# droneMaster.net
KiCad netlist of a schematic drawn in EAGLE
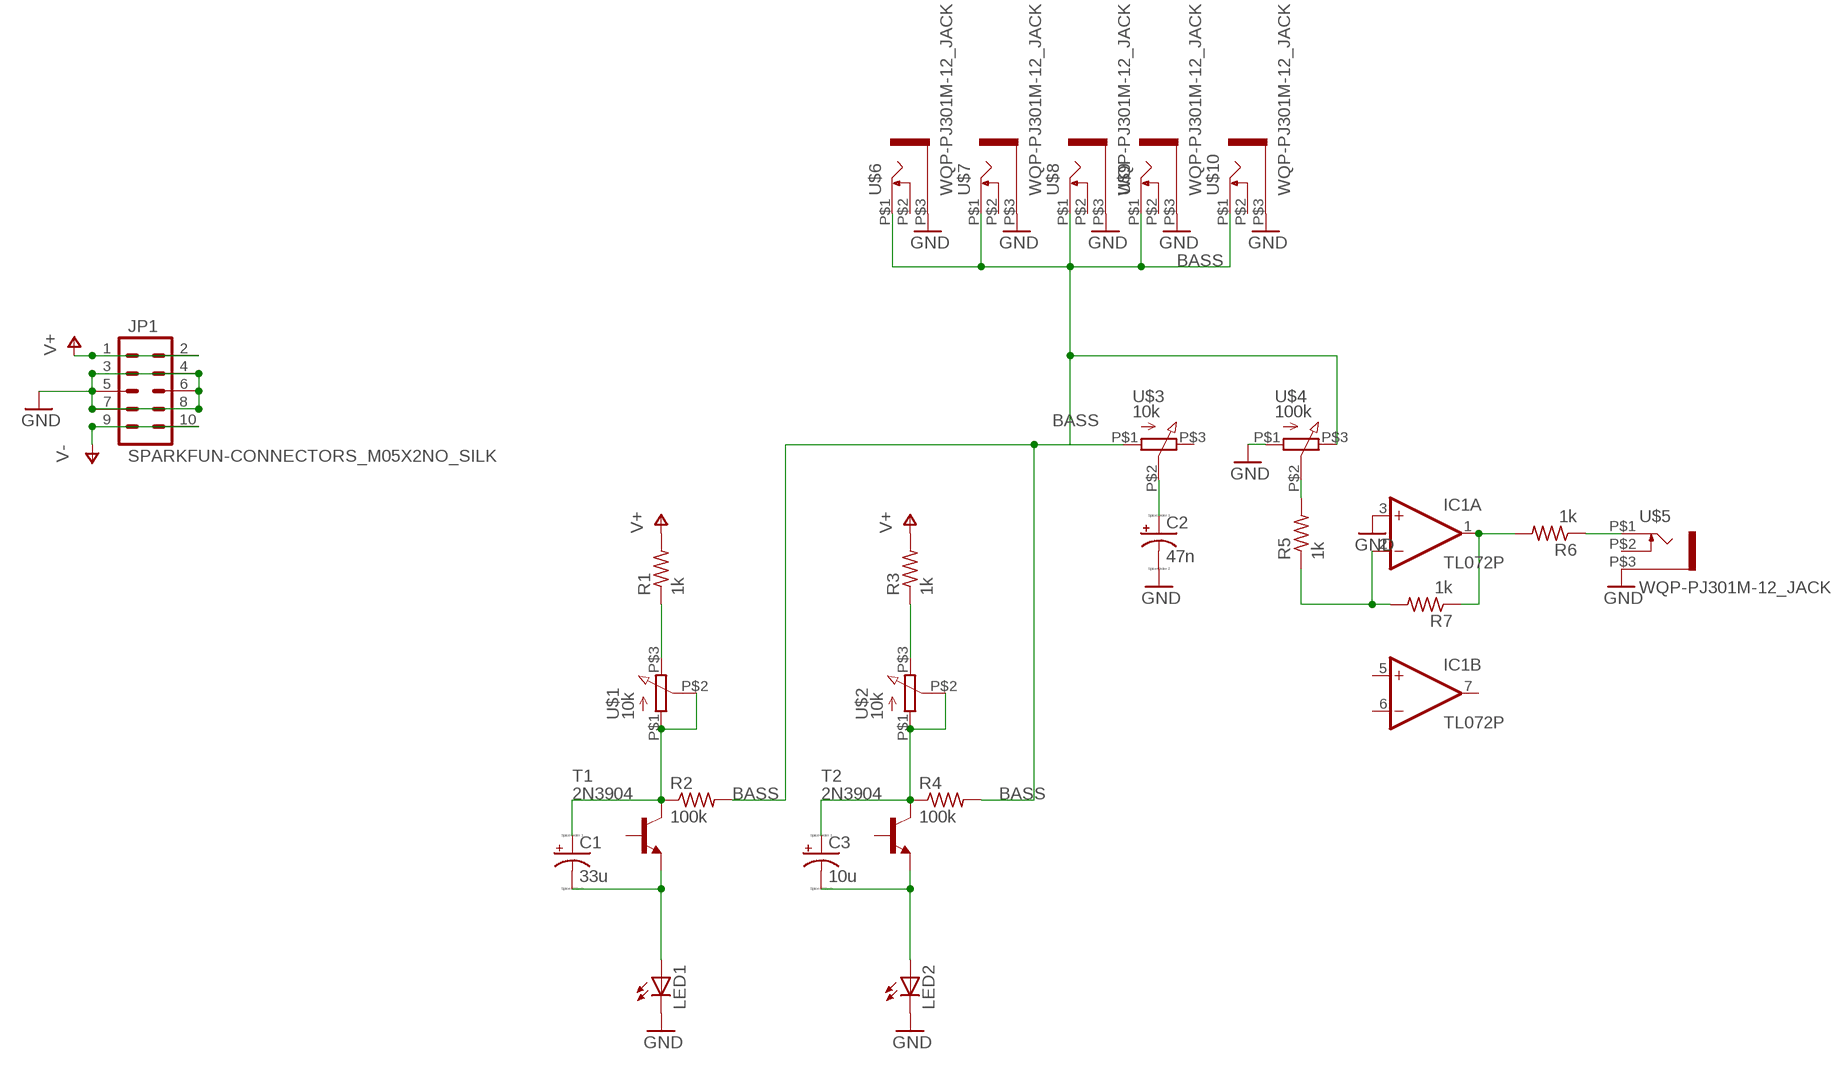
[diagram p0: schematic, sheet 1]

(export (version "E")
  (design (tool "Eeschema 10.0.6"))
  (components
    (comp (ref "C1")
      (value "33u")
      (footprint "eagle-import:E2,5-7")
      (libsource (lib "eagle-import") (part "CPOL-USE2.5-7"))
    )
    (comp (ref "C2")
      (value "47n")
      (footprint "eagle-import:E2,5-7")
      (libsource (lib "eagle-import") (part "CPOL-USE2.5-7"))
    )
    (comp (ref "C3")
      (value "10u")
      (footprint "eagle-import:E2,5-7")
      (libsource (lib "eagle-import") (part "CPOL-USE2.5-7"))
    )
    (comp (ref "IC1")
      (value "TL072P")
      (footprint "eagle-import:DIL08")
      (libsource (lib "eagle-import") (part "TL072P"))
    )
    (comp (ref "JP1")
      (value "SPARKFUN-CONNECTORS_M05X2NO_SILK")
      (footprint "eagle-import:SPARKFUN-CONNECTORS_2X5_NOSILK")
      (libsource (lib "eagle-import") (part "SPARKFUN-CONNECTORS_M05X2NO_SILK"))
    )
    (comp (ref "LED1")
      (value "LED5MM")
      (footprint "eagle-import:LED5MM")
      (libsource (lib "eagle-import") (part "LED5MM"))
    )
    (comp (ref "LED2")
      (value "LED5MM")
      (footprint "eagle-import:LED5MM")
      (libsource (lib "eagle-import") (part "LED5MM"))
    )
    (comp (ref "R1")
      (value "1k")
      (footprint "eagle-import:0204_7")
      (libsource (lib "eagle-import") (part "R-US_0204/7"))
    )
    (comp (ref "R2")
      (value "100k")
      (footprint "eagle-import:0204_7")
      (libsource (lib "eagle-import") (part "R-US_0204/7"))
    )
    (comp (ref "R3")
      (value "1k")
      (footprint "eagle-import:0204_7")
      (libsource (lib "eagle-import") (part "R-US_0204/7"))
    )
    (comp (ref "R4")
      (value "100k")
      (footprint "eagle-import:0204_7")
      (libsource (lib "eagle-import") (part "R-US_0204/7"))
    )
    (comp (ref "R5")
      (value "1k")
      (footprint "eagle-import:0204_7")
      (libsource (lib "eagle-import") (part "R-US_0204/7"))
    )
    (comp (ref "R6")
      (value "1k")
      (footprint "eagle-import:0204_7")
      (libsource (lib "eagle-import") (part "R-US_0204/7"))
    )
    (comp (ref "R7")
      (value "1k")
      (footprint "eagle-import:0204_7")
      (libsource (lib "eagle-import") (part "R-US_0204/7"))
    )
    (comp (ref "T1")
      (value "2N3904")
      (footprint "eagle-import:TO92")
      (libsource (lib "eagle-import") (part "2N3904"))
    )
    (comp (ref "T2")
      (value "2N3904")
      (footprint "eagle-import:TO92")
      (libsource (lib "eagle-import") (part "2N3904"))
    )
    (comp (ref "U$1")
      (value "10k")
      (footprint "eagle-import:INSTRUO_Q-POT")
      (libsource (lib "eagle-import") (part "INSTRUO_Q-POT"))
    )
    (comp (ref "U$2")
      (value "10k")
      (footprint "eagle-import:INSTRUO_Q-POT")
      (libsource (lib "eagle-import") (part "INSTRUO_Q-POT"))
    )
    (comp (ref "U$3")
      (value "10k")
      (footprint "eagle-import:INSTRUO_Q-POT")
      (libsource (lib "eagle-import") (part "INSTRUO_Q-POT"))
    )
    (comp (ref "U$4")
      (value "100k")
      (footprint "eagle-import:INSTRUO_Q-POT")
      (libsource (lib "eagle-import") (part "INSTRUO_Q-POT"))
    )
    (comp (ref "U$5")
      (value "WQP-PJ301M-12_JACK")
      (footprint "eagle-import:WQP-PJ301M-12_JACK")
      (libsource (lib "eagle-import") (part "WQP-PJ301M-12_JACK"))
    )
    (comp (ref "U$6")
      (value "WQP-PJ301M-12_JACK")
      (footprint "eagle-import:WQP-PJ301M-12_JACK")
      (libsource (lib "eagle-import") (part "WQP-PJ301M-12_JACK"))
    )
    (comp (ref "U$7")
      (value "WQP-PJ301M-12_JACK")
      (footprint "eagle-import:WQP-PJ301M-12_JACK")
      (libsource (lib "eagle-import") (part "WQP-PJ301M-12_JACK"))
    )
    (comp (ref "U$8")
      (value "WQP-PJ301M-12_JACK")
      (footprint "eagle-import:WQP-PJ301M-12_JACK")
      (libsource (lib "eagle-import") (part "WQP-PJ301M-12_JACK"))
    )
    (comp (ref "U$9")
      (value "WQP-PJ301M-12_JACK")
      (footprint "eagle-import:WQP-PJ301M-12_JACK")
      (libsource (lib "eagle-import") (part "WQP-PJ301M-12_JACK"))
    )
    (comp (ref "U$10")
      (value "WQP-PJ301M-12_JACK")
      (footprint "eagle-import:WQP-PJ301M-12_JACK")
      (libsource (lib "eagle-import") (part "WQP-PJ301M-12_JACK"))
    )
  )
  (nets
    (net (code "1") (name "/BASS") (class "Default")
      (node (ref "R2") (pin "2") (pinfunction "2_2") (pintype "passive"))
      (node (ref "R4") (pin "2") (pinfunction "2_2") (pintype "passive"))
      (node (ref "U$10") (pin "P$1") (pinfunction "2_P$1") (pintype "passive"))
      (node (ref "U$3") (pin "P$1") (pinfunction "1_P$1") (pintype "passive"))
      (node (ref "U$4") (pin "P$3") (pinfunction "3_P$3") (pintype "passive"))
      (node (ref "U$6") (pin "P$1") (pinfunction "2_P$1") (pintype "passive"))
      (node (ref "U$7") (pin "P$1") (pinfunction "2_P$1") (pintype "passive"))
      (node (ref "U$8") (pin "P$1") (pinfunction "2_P$1") (pintype "passive"))
      (node (ref "U$9") (pin "P$1") (pinfunction "2_P$1") (pintype "passive"))
    )
    (net (code "2") (name "GND") (class "Default")
      (node (ref "C2") (pin "-") (pinfunction "-_-") (pintype "passive"))
      (node (ref "IC1") (pin "3") (pinfunction "+IN_3") (pintype "input"))
      (node (ref "JP1") (pin "3") (pinfunction "3_3") (pintype "passive"))
      (node (ref "JP1") (pin "4") (pinfunction "4_4") (pintype "passive"))
      (node (ref "JP1") (pin "5") (pinfunction "5_5") (pintype "passive"))
      (node (ref "JP1") (pin "6") (pinfunction "6_6") (pintype "passive"))
      (node (ref "JP1") (pin "7") (pinfunction "7_7") (pintype "passive"))
      (node (ref "JP1") (pin "8") (pinfunction "8_8") (pintype "passive"))
      (node (ref "LED1") (pin "K") (pinfunction "C_K") (pintype "passive"))
      (node (ref "LED2") (pin "K") (pinfunction "C_K") (pintype "passive"))
      (node (ref "U$10") (pin "P$3") (pinfunction "1_P$3") (pintype "passive"))
      (node (ref "U$4") (pin "P$1") (pinfunction "1_P$1") (pintype "passive"))
      (node (ref "U$5") (pin "P$3") (pinfunction "1_P$3") (pintype "passive"))
      (node (ref "U$6") (pin "P$3") (pinfunction "1_P$3") (pintype "passive"))
      (node (ref "U$7") (pin "P$3") (pinfunction "1_P$3") (pintype "passive"))
      (node (ref "U$8") (pin "P$3") (pinfunction "1_P$3") (pintype "passive"))
      (node (ref "U$9") (pin "P$3") (pinfunction "1_P$3") (pintype "passive"))
    )
    (net (code "3") (name "Net-(IC1A--IN)") (class "Default")
      (node (ref "IC1") (pin "2") (pinfunction "-IN_2") (pintype "input"))
      (node (ref "R5") (pin "1") (pinfunction "1_1") (pintype "passive"))
      (node (ref "R7") (pin "2") (pinfunction "2_2") (pintype "passive"))
    )
    (net (code "4") (name "Net-(IC1A-OUT)") (class "Default")
      (node (ref "IC1") (pin "1") (pinfunction "OUT_1") (pintype "output"))
      (node (ref "R6") (pin "2") (pinfunction "2_2") (pintype "passive"))
      (node (ref "R7") (pin "1") (pinfunction "1_1") (pintype "passive"))
    )
    (net (code "5") (name "Net-(T1-C)") (class "Default")
      (node (ref "C1") (pin "+") (pinfunction "+_+") (pintype "passive"))
      (node (ref "R2") (pin "1") (pinfunction "1_1") (pintype "passive"))
      (node (ref "T1") (pin "1") (pinfunction "C_1") (pintype "passive"))
      (node (ref "U$1") (pin "P$1") (pinfunction "1_P$1") (pintype "passive"))
      (node (ref "U$1") (pin "P$2") (pinfunction "2_P$2") (pintype "passive"))
    )
    (net (code "6") (name "Net-(T1-E)") (class "Default")
      (node (ref "C1") (pin "-") (pinfunction "-_-") (pintype "passive"))
      (node (ref "LED1") (pin "A") (pinfunction "A_A") (pintype "passive"))
      (node (ref "T1") (pin "3") (pinfunction "E_3") (pintype "passive"))
    )
    (net (code "7") (name "Net-(T2-C)") (class "Default")
      (node (ref "C3") (pin "+") (pinfunction "+_+") (pintype "passive"))
      (node (ref "R4") (pin "1") (pinfunction "1_1") (pintype "passive"))
      (node (ref "T2") (pin "1") (pinfunction "C_1") (pintype "passive"))
      (node (ref "U$2") (pin "P$1") (pinfunction "1_P$1") (pintype "passive"))
      (node (ref "U$2") (pin "P$2") (pinfunction "2_P$2") (pintype "passive"))
    )
    (net (code "8") (name "Net-(T2-E)") (class "Default")
      (node (ref "C3") (pin "-") (pinfunction "-_-") (pintype "passive"))
      (node (ref "LED2") (pin "A") (pinfunction "A_A") (pintype "passive"))
      (node (ref "T2") (pin "3") (pinfunction "E_3") (pintype "passive"))
    )
    (net (code "9") (name "Net-(U$1-3)") (class "Default")
      (node (ref "R1") (pin "1") (pinfunction "1_1") (pintype "passive"))
      (node (ref "U$1") (pin "P$3") (pinfunction "3_P$3") (pintype "passive"))
    )
    (net (code "10") (name "Net-(U$2-3)") (class "Default")
      (node (ref "R3") (pin "1") (pinfunction "1_1") (pintype "passive"))
      (node (ref "U$2") (pin "P$3") (pinfunction "3_P$3") (pintype "passive"))
    )
    (net (code "11") (name "Net-(U$3-2)") (class "Default")
      (node (ref "C2") (pin "+") (pinfunction "+_+") (pintype "passive"))
      (node (ref "U$3") (pin "P$2") (pinfunction "2_P$2") (pintype "passive"))
    )
    (net (code "12") (name "Net-(U$4-2)") (class "Default")
      (node (ref "R5") (pin "2") (pinfunction "2_2") (pintype "passive"))
      (node (ref "U$4") (pin "P$2") (pinfunction "2_P$2") (pintype "passive"))
    )
    (net (code "13") (name "Net-(U$5-2)") (class "Default")
      (node (ref "R6") (pin "1") (pinfunction "1_1") (pintype "passive"))
      (node (ref "U$5") (pin "P$1") (pinfunction "2_P$1") (pintype "passive"))
    )
    (net (code "14") (name "V+") (class "Default")
      (node (ref "JP1") (pin "1") (pinfunction "1_1") (pintype "passive"))
      (node (ref "JP1") (pin "2") (pinfunction "2_2") (pintype "passive"))
      (node (ref "R1") (pin "2") (pinfunction "2_2") (pintype "passive"))
      (node (ref "R3") (pin "2") (pinfunction "2_2") (pintype "passive"))
    )
    (net (code "15") (name "V-") (class "Default")
      (node (ref "JP1") (pin "10") (pinfunction "10_10") (pintype "passive"))
      (node (ref "JP1") (pin "9") (pinfunction "9_9") (pintype "passive"))
    )
    (net (code "16") (name "unconnected-(IC1B-+IN-Pad5)") (class "Default")
      (node (ref "IC1") (pin "5") (pinfunction "+IN_5") (pintype "input"))
    )
    (net (code "17") (name "unconnected-(IC1B--IN-Pad6)") (class "Default")
      (node (ref "IC1") (pin "6") (pinfunction "-IN_6") (pintype "input"))
    )
    (net (code "18") (name "unconnected-(IC1B-OUT-Pad7)") (class "Default")
      (node (ref "IC1") (pin "7") (pinfunction "OUT_7") (pintype "output"))
    )
    (net (code "19") (name "unconnected-(T1-B-Pad2)") (class "Default")
      (node (ref "T1") (pin "2") (pinfunction "B_2") (pintype "passive"))
    )
    (net (code "20") (name "unconnected-(T2-B-Pad2)") (class "Default")
      (node (ref "T2") (pin "2") (pinfunction "B_2") (pintype "passive"))
    )
    (net (code "21") (name "unconnected-(U$3-3-PadP$3)") (class "Default")
      (node (ref "U$3") (pin "P$3") (pinfunction "3_P$3") (pintype "passive"))
    )
    (net (code "22") (name "unconnected-(U$5-3-PadP$2)") (class "Default")
      (node (ref "U$5") (pin "P$2") (pinfunction "3_P$2") (pintype "passive"))
    )
    (net (code "23") (name "unconnected-(U$6-3-PadP$2)") (class "Default")
      (node (ref "U$6") (pin "P$2") (pinfunction "3_P$2") (pintype "passive"))
    )
    (net (code "24") (name "unconnected-(U$7-3-PadP$2)") (class "Default")
      (node (ref "U$7") (pin "P$2") (pinfunction "3_P$2") (pintype "passive"))
    )
    (net (code "25") (name "unconnected-(U$8-3-PadP$2)") (class "Default")
      (node (ref "U$8") (pin "P$2") (pinfunction "3_P$2") (pintype "passive"))
    )
    (net (code "26") (name "unconnected-(U$9-3-PadP$2)") (class "Default")
      (node (ref "U$9") (pin "P$2") (pinfunction "3_P$2") (pintype "passive"))
    )
    (net (code "27") (name "unconnected-(U$10-3-PadP$2)") (class "Default")
      (node (ref "U$10") (pin "P$2") (pinfunction "3_P$2") (pintype "passive"))
    )
  )
)
